# ProDoc_ChisFlash-Prometheus-1_0.net
KiCad netlist of a schematic drawn in EasyEDA Pro
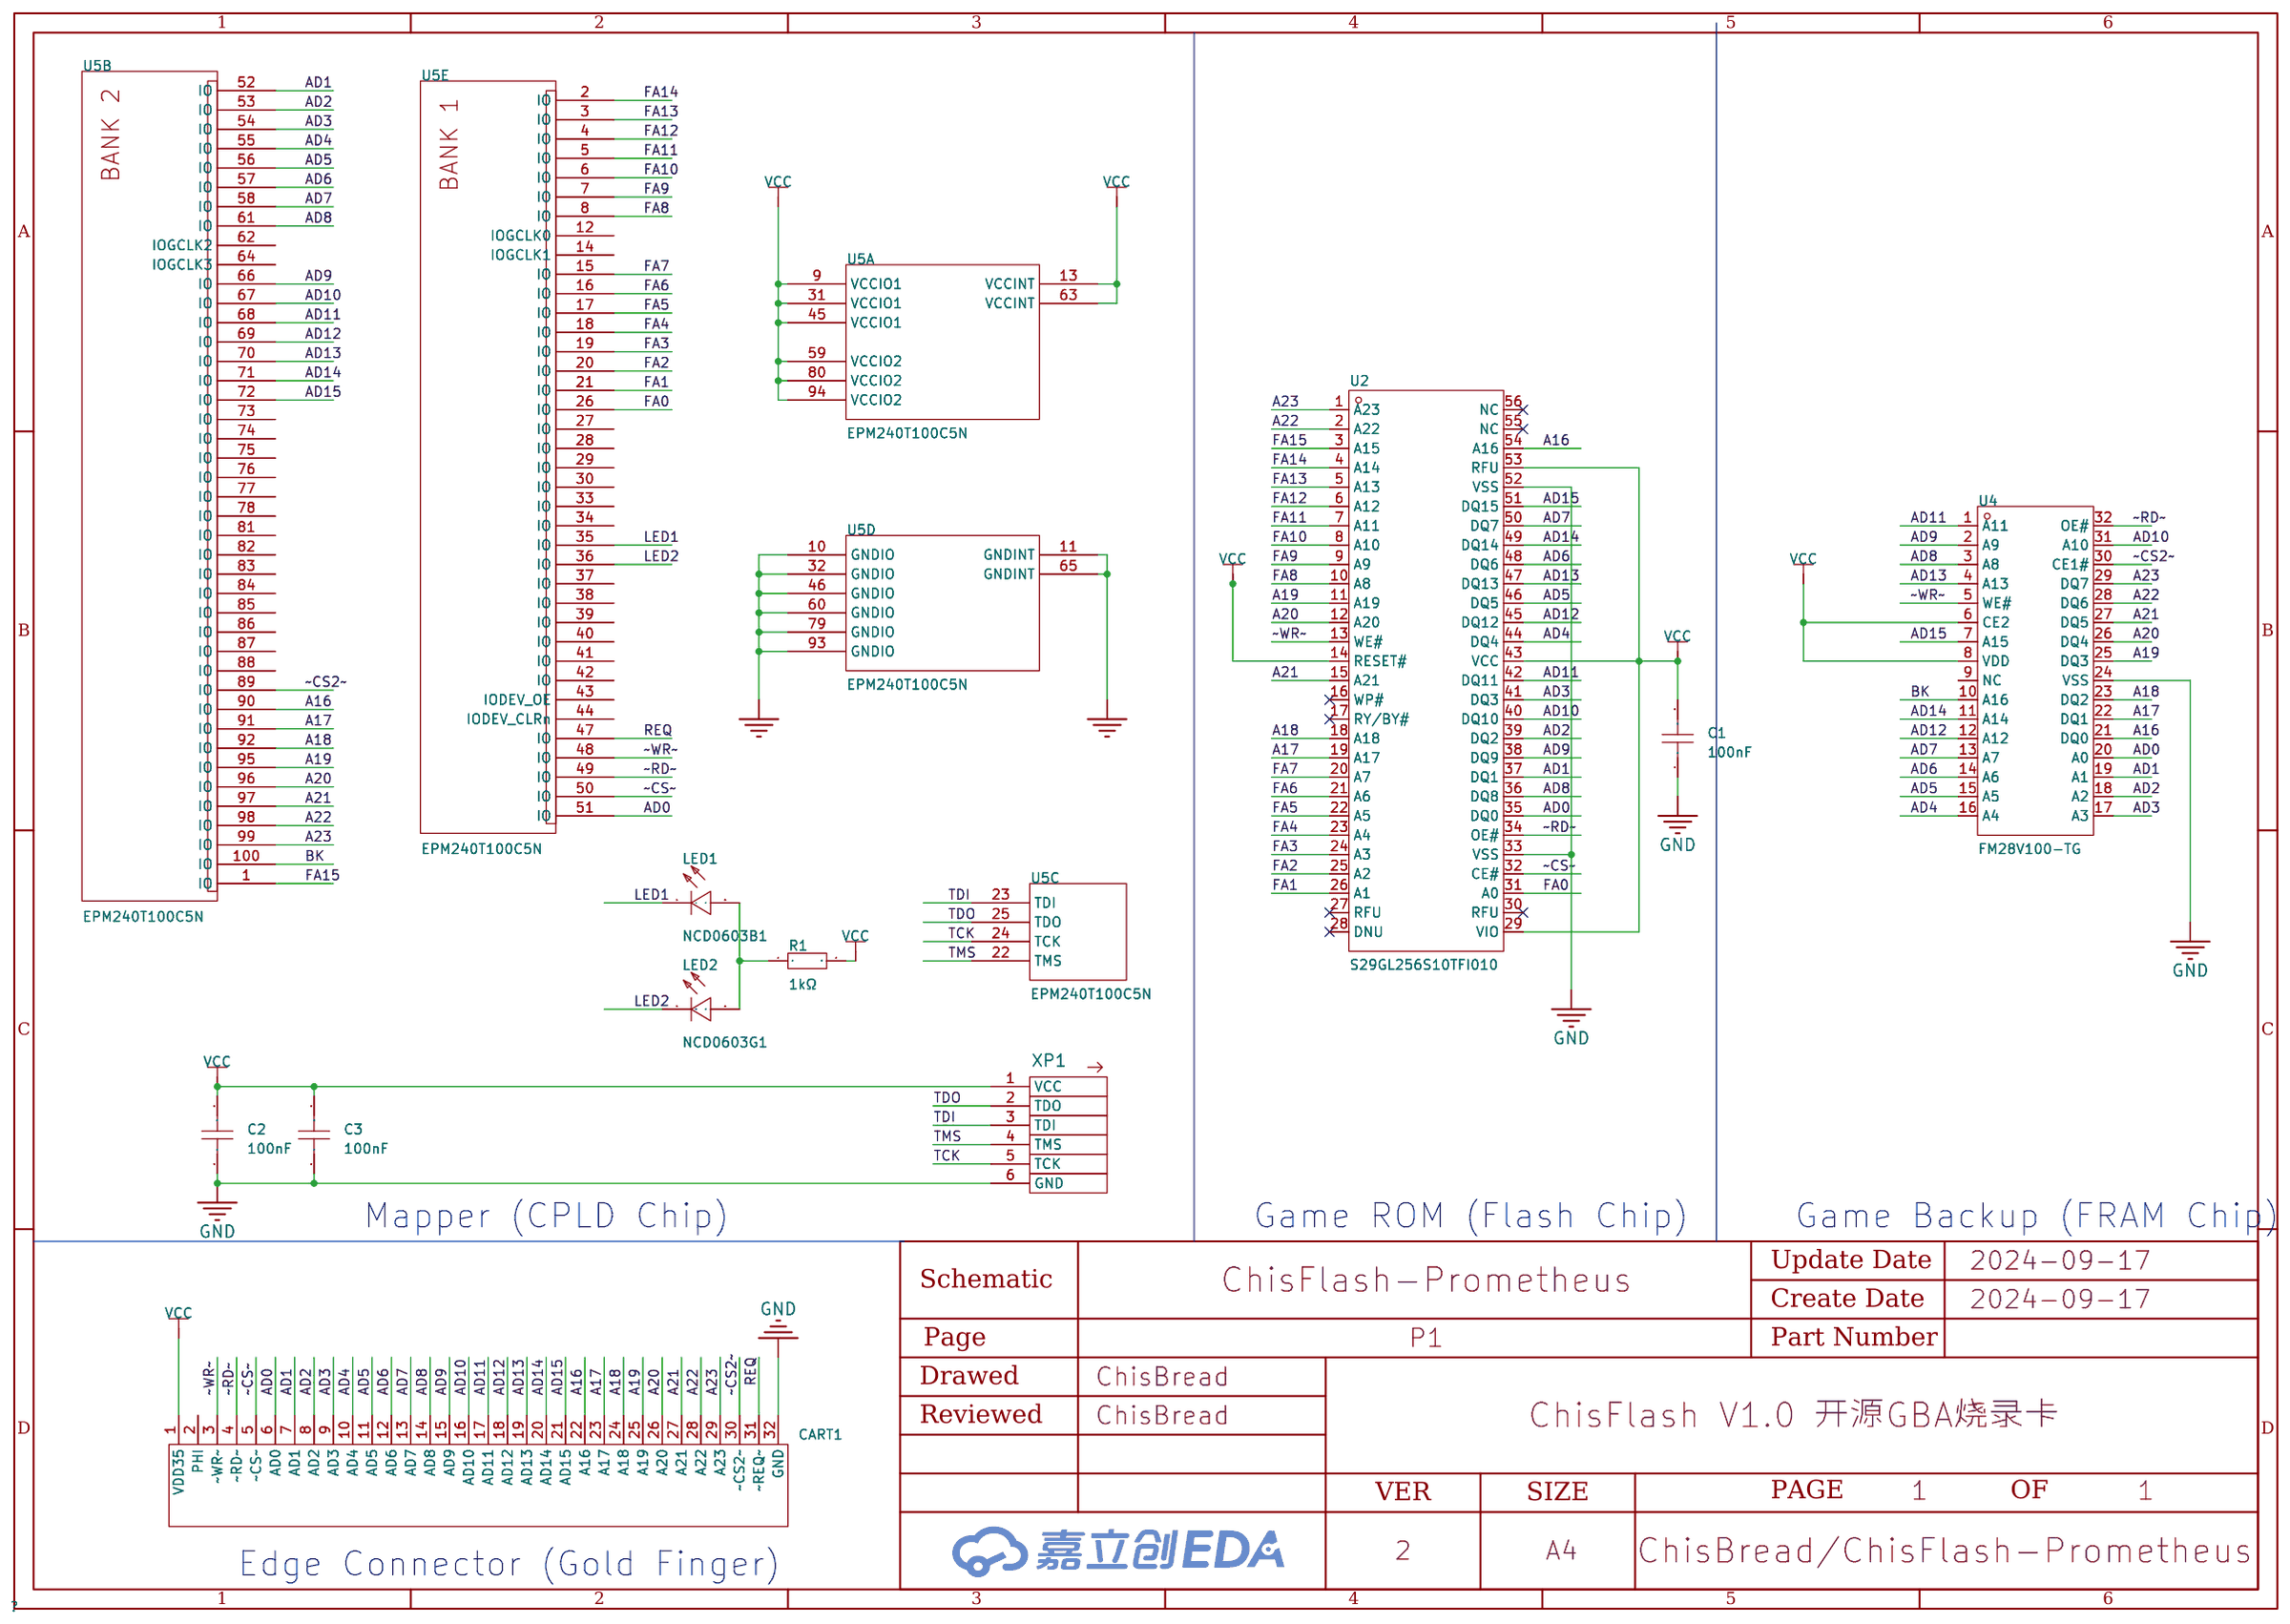
[diagram p0: schematic sheet]

(export (version "E")
  (design (tool "Eeschema 10.0.6"))
  (components
    (comp (ref "C1")
      (value "100nF")
      (footprint "easyedapro:C0603")
      (libsource (lib "easyedapro") (part "CapAcitance"))
    )
    (comp (ref "C2")
      (value "100nF")
      (footprint "easyedapro:C0603")
      (libsource (lib "easyedapro") (part "CapAcitance"))
    )
    (comp (ref "C3")
      (value "100nF")
      (footprint "easyedapro:C0603")
      (libsource (lib "easyedapro") (part "CapAcitance"))
    )
    (comp (ref "CART1")
      (value "~")
      (footprint "easyedapro:GBA卡带金手指")
      (description "GBA卡带金手指")
      (libsource (lib "easyedapro") (part "GBA卡带金手指"))
    )
    (comp (ref "LED1")
      (value "NCD0603B1")
      (footprint "easyedapro:LED0603-RD")
      (fields (field (name "Manufacturer") "国星光电"))
      (libsource (lib "easyedapro") (part "FC-DA1608BK-470H10"))
    )
    (comp (ref "LED2")
      (value "NCD0603G1")
      (footprint "easyedapro:LED0603-RD")
      (fields (field (name "Manufacturer") "国星光电"))
      (libsource (lib "easyedapro") (part "FC-D1608UGK-520D10"))
    )
    (comp (ref "R1")
      (value "1kΩ")
      (footprint "easyedapro:R0603")
      (description "电阻类型:厚膜电阻;阻值:1kΩ;精度:±1%;功率:100mW;最大工作电压:75V;温度系数:±100ppm/°C;")
      (fields
        (field (name "Manufacturer Part") "0603WAF1001T5E")
        (field (name "Manufacturer") "UNI-ROYAL(厚声)")
      )
      (libsource (lib "easyedapro") (part "0603WAF1001T5E"))
    )
    (comp (ref "U2")
      (value "S29GL256S10TFI010")
      (footprint "easyedapro:TSOP-56_L18.4-W14.0-P0.50-LS20.0-TL")
      (fields (field (name "Manufacturer") "SPANSION(飞索)"))
      (libsource (lib "easyedapro") (part "S29GL256S10TFI010"))
    )
    (comp (ref "U4")
      (value "FM28V100-TG")
      (fields (field (name "Manufacturer") "CYPRESS(赛普拉斯)"))
      (libsource (lib "easyedapro") (part "FM28V100-TG_C2959453"))
    )
    (comp (ref "U5")
      (value "EPM240T100C5N")
      (footprint "easyedapro:TQFP-100_L14.0-W14.0-P0.50-LS16.0-BL")
      (description "类型:其它PLD;逻辑门数量:-;逻辑单元数:-;逻辑阵列块数:240;")
      (fields (field (name "Manufacturer") "Intel/Altera"))
      (libsource (lib "easyedapro") (part "EPM240T100C5N"))
    )
    (comp (ref "XP1")
      (value "JTAG")
      (footprint "easyedapro:HDR-TH_6P-P1.27-V-M-1")
      (libsource (lib "easyedapro") (part "jtag"))
    )
  )
  (nets
    (net (code "1") (name "/A16") (class "Default")
      (node (ref "CART1") (pin "22") (pinfunction "A16_22") (pintype "input"))
      (node (ref "U2") (pin "54") (pinfunction "A16_54") (pintype "input"))
      (node (ref "U4") (pin "21") (pinfunction "DQ0_21") (pintype "unspecified"))
      (node (ref "U5") (pin "90") (pinfunction "IO_90") (pintype "bidirectional"))
    )
    (net (code "2") (name "/A17") (class "Default")
      (node (ref "CART1") (pin "23") (pinfunction "A17_23") (pintype "input"))
      (node (ref "U2") (pin "19") (pinfunction "A17_19") (pintype "input"))
      (node (ref "U4") (pin "22") (pinfunction "DQ1_22") (pintype "unspecified"))
      (node (ref "U5") (pin "91") (pinfunction "IO_91") (pintype "bidirectional"))
    )
    (net (code "3") (name "/A18") (class "Default")
      (node (ref "CART1") (pin "24") (pinfunction "A18_24") (pintype "input"))
      (node (ref "U2") (pin "18") (pinfunction "A18_18") (pintype "input"))
      (node (ref "U4") (pin "23") (pinfunction "DQ2_23") (pintype "unspecified"))
      (node (ref "U5") (pin "92") (pinfunction "IO_92") (pintype "bidirectional"))
    )
    (net (code "4") (name "/A19") (class "Default")
      (node (ref "CART1") (pin "25") (pinfunction "A19_25") (pintype "input"))
      (node (ref "U2") (pin "11") (pinfunction "A19_11") (pintype "input"))
      (node (ref "U4") (pin "25") (pinfunction "DQ3_25") (pintype "unspecified"))
      (node (ref "U5") (pin "95") (pinfunction "IO_95") (pintype "bidirectional"))
    )
    (net (code "5") (name "/A20") (class "Default")
      (node (ref "CART1") (pin "26") (pinfunction "A20_26") (pintype "input"))
      (node (ref "U2") (pin "12") (pinfunction "A20_12") (pintype "input"))
      (node (ref "U4") (pin "26") (pinfunction "DQ4_26") (pintype "unspecified"))
      (node (ref "U5") (pin "96") (pinfunction "IO_96") (pintype "bidirectional"))
    )
    (net (code "6") (name "/A21") (class "Default")
      (node (ref "CART1") (pin "27") (pinfunction "A21_27") (pintype "input"))
      (node (ref "U2") (pin "15") (pinfunction "A21_15") (pintype "input"))
      (node (ref "U4") (pin "27") (pinfunction "DQ5_27") (pintype "unspecified"))
      (node (ref "U5") (pin "97") (pinfunction "IO_97") (pintype "bidirectional"))
    )
    (net (code "7") (name "/A22") (class "Default")
      (node (ref "CART1") (pin "28") (pinfunction "A22_28") (pintype "input"))
      (node (ref "U2") (pin "2") (pinfunction "A22_2") (pintype "input"))
      (node (ref "U4") (pin "28") (pinfunction "DQ6_28") (pintype "unspecified"))
      (node (ref "U5") (pin "98") (pinfunction "IO_98") (pintype "bidirectional"))
    )
    (net (code "8") (name "/A23") (class "Default")
      (node (ref "CART1") (pin "29") (pinfunction "A23_29") (pintype "input"))
      (node (ref "U2") (pin "1") (pinfunction "A23_1") (pintype "input"))
      (node (ref "U4") (pin "29") (pinfunction "DQ7_29") (pintype "unspecified"))
      (node (ref "U5") (pin "99") (pinfunction "IO_99") (pintype "bidirectional"))
    )
    (net (code "9") (name "/AD0") (class "Default")
      (node (ref "CART1") (pin "6") (pinfunction "AD0_6") (pintype "input"))
      (node (ref "U2") (pin "35") (pinfunction "DQ0_35") (pintype "input"))
      (node (ref "U4") (pin "20") (pinfunction "A0_20") (pintype "unspecified"))
      (node (ref "U5") (pin "51") (pinfunction "IO_51") (pintype "bidirectional"))
    )
    (net (code "10") (name "/AD1") (class "Default")
      (node (ref "CART1") (pin "7") (pinfunction "AD1_7") (pintype "input"))
      (node (ref "U2") (pin "37") (pinfunction "DQ1_37") (pintype "input"))
      (node (ref "U4") (pin "19") (pinfunction "A1_19") (pintype "unspecified"))
      (node (ref "U5") (pin "52") (pinfunction "IO_52") (pintype "bidirectional"))
    )
    (net (code "11") (name "/AD2") (class "Default")
      (node (ref "CART1") (pin "8") (pinfunction "AD2_8") (pintype "input"))
      (node (ref "U2") (pin "39") (pinfunction "DQ2_39") (pintype "input"))
      (node (ref "U4") (pin "18") (pinfunction "A2_18") (pintype "unspecified"))
      (node (ref "U5") (pin "53") (pinfunction "IO_53") (pintype "bidirectional"))
    )
    (net (code "12") (name "/AD3") (class "Default")
      (node (ref "CART1") (pin "9") (pinfunction "AD3_9") (pintype "input"))
      (node (ref "U2") (pin "41") (pinfunction "DQ3_41") (pintype "input"))
      (node (ref "U4") (pin "17") (pinfunction "A3_17") (pintype "unspecified"))
      (node (ref "U5") (pin "54") (pinfunction "IO_54") (pintype "bidirectional"))
    )
    (net (code "13") (name "/AD4") (class "Default")
      (node (ref "CART1") (pin "10") (pinfunction "AD4_10") (pintype "input"))
      (node (ref "U2") (pin "44") (pinfunction "DQ4_44") (pintype "input"))
      (node (ref "U4") (pin "16") (pinfunction "A4_16") (pintype "unspecified"))
      (node (ref "U5") (pin "55") (pinfunction "IO_55") (pintype "bidirectional"))
    )
    (net (code "14") (name "/AD5") (class "Default")
      (node (ref "CART1") (pin "11") (pinfunction "AD5_11") (pintype "input"))
      (node (ref "U2") (pin "46") (pinfunction "DQ5_46") (pintype "input"))
      (node (ref "U4") (pin "15") (pinfunction "A5_15") (pintype "unspecified"))
      (node (ref "U5") (pin "56") (pinfunction "IO_56") (pintype "bidirectional"))
    )
    (net (code "15") (name "/AD6") (class "Default")
      (node (ref "CART1") (pin "12") (pinfunction "AD6_12") (pintype "input"))
      (node (ref "U2") (pin "48") (pinfunction "DQ6_48") (pintype "input"))
      (node (ref "U4") (pin "14") (pinfunction "A6_14") (pintype "unspecified"))
      (node (ref "U5") (pin "57") (pinfunction "IO_57") (pintype "bidirectional"))
    )
    (net (code "16") (name "/AD7") (class "Default")
      (node (ref "CART1") (pin "13") (pinfunction "AD7_13") (pintype "input"))
      (node (ref "U2") (pin "50") (pinfunction "DQ7_50") (pintype "input"))
      (node (ref "U4") (pin "13") (pinfunction "A7_13") (pintype "unspecified"))
      (node (ref "U5") (pin "58") (pinfunction "IO_58") (pintype "bidirectional"))
    )
    (net (code "17") (name "/AD8") (class "Default")
      (node (ref "CART1") (pin "14") (pinfunction "AD8_14") (pintype "input"))
      (node (ref "U2") (pin "36") (pinfunction "DQ8_36") (pintype "input"))
      (node (ref "U4") (pin "3") (pinfunction "A8_3") (pintype "unspecified"))
      (node (ref "U5") (pin "61") (pinfunction "IO_61") (pintype "bidirectional"))
    )
    (net (code "18") (name "/AD9") (class "Default")
      (node (ref "CART1") (pin "15") (pinfunction "AD9_15") (pintype "input"))
      (node (ref "U2") (pin "38") (pinfunction "DQ9_38") (pintype "input"))
      (node (ref "U4") (pin "2") (pinfunction "A9_2") (pintype "unspecified"))
      (node (ref "U5") (pin "66") (pinfunction "IO_66") (pintype "bidirectional"))
    )
    (net (code "19") (name "/AD10") (class "Default")
      (node (ref "CART1") (pin "16") (pinfunction "AD10_16") (pintype "input"))
      (node (ref "U2") (pin "40") (pinfunction "DQ10_40") (pintype "input"))
      (node (ref "U4") (pin "31") (pinfunction "A10_31") (pintype "unspecified"))
      (node (ref "U5") (pin "67") (pinfunction "IO_67") (pintype "bidirectional"))
    )
    (net (code "20") (name "/AD11") (class "Default")
      (node (ref "CART1") (pin "17") (pinfunction "AD11_17") (pintype "input"))
      (node (ref "U2") (pin "42") (pinfunction "DQ11_42") (pintype "input"))
      (node (ref "U4") (pin "1") (pinfunction "A11_1") (pintype "unspecified"))
      (node (ref "U5") (pin "68") (pinfunction "IO_68") (pintype "bidirectional"))
    )
    (net (code "21") (name "/AD12") (class "Default")
      (node (ref "CART1") (pin "18") (pinfunction "AD12_18") (pintype "input"))
      (node (ref "U2") (pin "45") (pinfunction "DQ12_45") (pintype "input"))
      (node (ref "U4") (pin "12") (pinfunction "A12_12") (pintype "unspecified"))
      (node (ref "U5") (pin "69") (pinfunction "IO_69") (pintype "bidirectional"))
    )
    (net (code "22") (name "/AD13") (class "Default")
      (node (ref "CART1") (pin "19") (pinfunction "AD13_19") (pintype "input"))
      (node (ref "U2") (pin "47") (pinfunction "DQ13_47") (pintype "input"))
      (node (ref "U4") (pin "4") (pinfunction "A13_4") (pintype "unspecified"))
      (node (ref "U5") (pin "70") (pinfunction "IO_70") (pintype "bidirectional"))
    )
    (net (code "23") (name "/AD14") (class "Default")
      (node (ref "CART1") (pin "20") (pinfunction "AD14_20") (pintype "input"))
      (node (ref "U2") (pin "49") (pinfunction "DQ14_49") (pintype "input"))
      (node (ref "U4") (pin "11") (pinfunction "A14_11") (pintype "unspecified"))
      (node (ref "U5") (pin "71") (pinfunction "IO_71") (pintype "bidirectional"))
    )
    (net (code "24") (name "/AD15") (class "Default")
      (node (ref "CART1") (pin "21") (pinfunction "AD15_21") (pintype "input"))
      (node (ref "U2") (pin "51") (pinfunction "DQ15_51") (pintype "input"))
      (node (ref "U4") (pin "7") (pinfunction "A15_7") (pintype "unspecified"))
      (node (ref "U5") (pin "72") (pinfunction "IO_72") (pintype "bidirectional"))
    )
    (net (code "25") (name "/BK") (class "Default")
      (node (ref "U4") (pin "10") (pinfunction "A16_10") (pintype "unspecified"))
      (node (ref "U5") (pin "100") (pinfunction "IO_100") (pintype "bidirectional"))
    )
    (net (code "26") (name "/FA0") (class "Default")
      (node (ref "U2") (pin "31") (pinfunction "A0_31") (pintype "input"))
      (node (ref "U5") (pin "26") (pinfunction "IO_26") (pintype "bidirectional"))
    )
    (net (code "27") (name "/FA1") (class "Default")
      (node (ref "U2") (pin "26") (pinfunction "A1_26") (pintype "input"))
      (node (ref "U5") (pin "21") (pinfunction "IO_21") (pintype "bidirectional"))
    )
    (net (code "28") (name "/FA2") (class "Default")
      (node (ref "U2") (pin "25") (pinfunction "A2_25") (pintype "input"))
      (node (ref "U5") (pin "20") (pinfunction "IO_20") (pintype "bidirectional"))
    )
    (net (code "29") (name "/FA3") (class "Default")
      (node (ref "U2") (pin "24") (pinfunction "A3_24") (pintype "input"))
      (node (ref "U5") (pin "19") (pinfunction "IO_19") (pintype "bidirectional"))
    )
    (net (code "30") (name "/FA4") (class "Default")
      (node (ref "U2") (pin "23") (pinfunction "A4_23") (pintype "input"))
      (node (ref "U5") (pin "18") (pinfunction "IO_18") (pintype "bidirectional"))
    )
    (net (code "31") (name "/FA5") (class "Default")
      (node (ref "U2") (pin "22") (pinfunction "A5_22") (pintype "input"))
      (node (ref "U5") (pin "17") (pinfunction "IO_17") (pintype "bidirectional"))
    )
    (net (code "32") (name "/FA6") (class "Default")
      (node (ref "U2") (pin "21") (pinfunction "A6_21") (pintype "input"))
      (node (ref "U5") (pin "16") (pinfunction "IO_16") (pintype "bidirectional"))
    )
    (net (code "33") (name "/FA7") (class "Default")
      (node (ref "U2") (pin "20") (pinfunction "A7_20") (pintype "input"))
      (node (ref "U5") (pin "15") (pinfunction "IO_15") (pintype "bidirectional"))
    )
    (net (code "34") (name "/FA8") (class "Default")
      (node (ref "U2") (pin "10") (pinfunction "A8_10") (pintype "input"))
      (node (ref "U5") (pin "8") (pinfunction "IO_8") (pintype "bidirectional"))
    )
    (net (code "35") (name "/FA9") (class "Default")
      (node (ref "U2") (pin "9") (pinfunction "A9_9") (pintype "input"))
      (node (ref "U5") (pin "7") (pinfunction "IO_7") (pintype "bidirectional"))
    )
    (net (code "36") (name "/FA10") (class "Default")
      (node (ref "U2") (pin "8") (pinfunction "A10_8") (pintype "input"))
      (node (ref "U5") (pin "6") (pinfunction "IO_6") (pintype "bidirectional"))
    )
    (net (code "37") (name "/FA11") (class "Default")
      (node (ref "U2") (pin "7") (pinfunction "A11_7") (pintype "input"))
      (node (ref "U5") (pin "5") (pinfunction "IO_5") (pintype "bidirectional"))
    )
    (net (code "38") (name "/FA12") (class "Default")
      (node (ref "U2") (pin "6") (pinfunction "A12_6") (pintype "input"))
      (node (ref "U5") (pin "4") (pinfunction "IO_4") (pintype "bidirectional"))
    )
    (net (code "39") (name "/FA13") (class "Default")
      (node (ref "U2") (pin "5") (pinfunction "A13_5") (pintype "input"))
      (node (ref "U5") (pin "3") (pinfunction "IO_3") (pintype "bidirectional"))
    )
    (net (code "40") (name "/FA14") (class "Default")
      (node (ref "U2") (pin "4") (pinfunction "A14_4") (pintype "input"))
      (node (ref "U5") (pin "2") (pinfunction "IO_2") (pintype "bidirectional"))
    )
    (net (code "41") (name "/FA15") (class "Default")
      (node (ref "U2") (pin "3") (pinfunction "A15_3") (pintype "input"))
      (node (ref "U5") (pin "1") (pinfunction "IO_1") (pintype "bidirectional"))
    )
    (net (code "42") (name "/LED1") (class "Default")
      (node (ref "LED1") (pin "1") (pinfunction "-_1") (pintype "input"))
      (node (ref "U5") (pin "35") (pinfunction "IO_35") (pintype "bidirectional"))
    )
    (net (code "43") (name "/LED2") (class "Default")
      (node (ref "LED2") (pin "1") (pinfunction "K_1") (pintype "input"))
      (node (ref "U5") (pin "36") (pinfunction "IO_36") (pintype "bidirectional"))
    )
    (net (code "44") (name "/REQ") (class "Default")
      (node (ref "CART1") (pin "31") (pinfunction "~REQ~_31") (pintype "input"))
      (node (ref "U5") (pin "47") (pinfunction "IO_47") (pintype "bidirectional"))
    )
    (net (code "45") (name "/TCK") (class "Default")
      (node (ref "U5") (pin "24") (pinfunction "TCK_24") (pintype "unspecified"))
      (node (ref "XP1") (pin "5") (pinfunction "TCK_5") (pintype "input"))
    )
    (net (code "46") (name "/TDI") (class "Default")
      (node (ref "U5") (pin "23") (pinfunction "TDI_23") (pintype "unspecified"))
      (node (ref "XP1") (pin "3") (pinfunction "TDI_3") (pintype "output"))
    )
    (net (code "47") (name "/TDO") (class "Default")
      (node (ref "U5") (pin "25") (pinfunction "TDO_25") (pintype "output"))
      (node (ref "XP1") (pin "2") (pinfunction "TDO_2") (pintype "output"))
    )
    (net (code "48") (name "/TMS") (class "Default")
      (node (ref "U5") (pin "22") (pinfunction "TMS_22") (pintype "unspecified"))
      (node (ref "XP1") (pin "4") (pinfunction "TMS_4") (pintype "output"))
    )
    (net (code "49") (name "/~CS2~") (class "Default")
      (node (ref "CART1") (pin "30") (pinfunction "~CS2~_30") (pintype "input"))
      (node (ref "U4") (pin "30") (pinfunction "CE1#_30") (pintype "unspecified"))
      (node (ref "U5") (pin "89") (pinfunction "IO_89") (pintype "bidirectional"))
    )
    (net (code "50") (name "/~CS~") (class "Default")
      (node (ref "CART1") (pin "5") (pinfunction "~CS~_5") (pintype "input"))
      (node (ref "U2") (pin "32") (pinfunction "CE#_32") (pintype "input"))
      (node (ref "U5") (pin "50") (pinfunction "IO_50") (pintype "bidirectional"))
    )
    (net (code "51") (name "/~RD~") (class "Default")
      (node (ref "CART1") (pin "4") (pinfunction "~RD~_4") (pintype "input"))
      (node (ref "U2") (pin "34") (pinfunction "OE#_34") (pintype "input"))
      (node (ref "U4") (pin "32") (pinfunction "OE#_32") (pintype "unspecified"))
      (node (ref "U5") (pin "49") (pinfunction "IO_49") (pintype "bidirectional"))
    )
    (net (code "52") (name "/~WR~") (class "Default")
      (node (ref "CART1") (pin "3") (pinfunction "~WR~_3") (pintype "input"))
      (node (ref "U2") (pin "13") (pinfunction "WE#_13") (pintype "input"))
      (node (ref "U4") (pin "5") (pinfunction "WE#_5") (pintype "unspecified"))
      (node (ref "U5") (pin "48") (pinfunction "IO_48") (pintype "bidirectional"))
    )
    (net (code "53") (name "GND") (class "Default")
      (node (ref "C1") (pin "1") (pinfunction "1_1") (pintype "input"))
      (node (ref "C2") (pin "1") (pinfunction "1_1") (pintype "input"))
      (node (ref "C3") (pin "1") (pinfunction "1_1") (pintype "input"))
      (node (ref "CART1") (pin "32") (pinfunction "GND_32") (pintype "input"))
      (node (ref "U2") (pin "33") (pinfunction "VSS_33") (pintype "input"))
      (node (ref "U2") (pin "52") (pinfunction "VSS_52") (pintype "input"))
      (node (ref "U4") (pin "24") (pinfunction "VSS_24") (pintype "unspecified"))
      (node (ref "U5") (pin "10") (pinfunction "GNDIO_10") (pintype "unspecified"))
      (node (ref "U5") (pin "11") (pinfunction "GNDINT_11") (pintype "unspecified"))
      (node (ref "U5") (pin "32") (pinfunction "GNDIO_32") (pintype "unspecified"))
      (node (ref "U5") (pin "46") (pinfunction "GNDIO_46") (pintype "unspecified"))
      (node (ref "U5") (pin "60") (pinfunction "GNDIO_60") (pintype "unspecified"))
      (node (ref "U5") (pin "65") (pinfunction "GNDINT_65") (pintype "unspecified"))
      (node (ref "U5") (pin "79") (pinfunction "GNDIO_79") (pintype "unspecified"))
      (node (ref "U5") (pin "93") (pinfunction "GNDIO_93") (pintype "unspecified"))
      (node (ref "XP1") (pin "6") (pinfunction "GND_6") (pintype "input"))
    )
    (net (code "54") (name "Net-(LED1-+)") (class "Default")
      (node (ref "LED1") (pin "2") (pinfunction "+_2") (pintype "input"))
      (node (ref "LED2") (pin "2") (pinfunction "A_2") (pintype "input"))
      (node (ref "R1") (pin "1") (pinfunction "1_1") (pintype "input"))
    )
    (net (code "55") (name "VCC") (class "Default")
      (node (ref "C1") (pin "2") (pinfunction "2_2") (pintype "input"))
      (node (ref "C2") (pin "2") (pinfunction "2_2") (pintype "input"))
      (node (ref "C3") (pin "2") (pinfunction "2_2") (pintype "input"))
      (node (ref "CART1") (pin "1") (pinfunction "VDD35_1") (pintype "input"))
      (node (ref "R1") (pin "2") (pinfunction "2_2") (pintype "input"))
      (node (ref "U2") (pin "14") (pinfunction "RESET#_14") (pintype "input"))
      (node (ref "U2") (pin "29") (pinfunction "VIO_29") (pintype "input"))
      (node (ref "U2") (pin "43") (pinfunction "VCC_43") (pintype "input"))
      (node (ref "U2") (pin "53") (pinfunction "RFU_53") (pintype "input"))
      (node (ref "U4") (pin "6") (pinfunction "CE2_6") (pintype "unspecified"))
      (node (ref "U4") (pin "8") (pinfunction "VDD_8") (pintype "unspecified"))
      (node (ref "U5") (pin "13") (pinfunction "VCCINT_13") (pintype "unspecified"))
      (node (ref "U5") (pin "31") (pinfunction "VCCIO1_31") (pintype "unspecified"))
      (node (ref "U5") (pin "45") (pinfunction "VCCIO1_45") (pintype "unspecified"))
      (node (ref "U5") (pin "59") (pinfunction "VCCIO2_59") (pintype "unspecified"))
      (node (ref "U5") (pin "63") (pinfunction "VCCINT_63") (pintype "unspecified"))
      (node (ref "U5") (pin "80") (pinfunction "VCCIO2_80") (pintype "unspecified"))
      (node (ref "U5") (pin "9") (pinfunction "VCCIO1_9") (pintype "unspecified"))
      (node (ref "U5") (pin "94") (pinfunction "VCCIO2_94") (pintype "unspecified"))
      (node (ref "XP1") (pin "1") (pinfunction "VCC_1") (pintype "output"))
    )
    (net (code "56") (name "unconnected-(CART1-PHI-Pad2)") (class "Default")
      (node (ref "CART1") (pin "2") (pinfunction "PHI_2") (pintype "input"))
    )
    (net (code "57") (name "unconnected-(U2-DNU-Pad28)") (class "Default")
      (node (ref "U2") (pin "28") (pinfunction "DNU_28") (pintype "input+no_connect"))
    )
    (net (code "58") (name "unconnected-(U2-NC-Pad55)") (class "Default")
      (node (ref "U2") (pin "55") (pinfunction "NC_55") (pintype "input+no_connect"))
    )
    (net (code "59") (name "unconnected-(U2-NC-Pad56)") (class "Default")
      (node (ref "U2") (pin "56") (pinfunction "NC_56") (pintype "input+no_connect"))
    )
    (net (code "60") (name "unconnected-(U2-RFU-Pad27)") (class "Default")
      (node (ref "U2") (pin "27") (pinfunction "RFU_27") (pintype "input+no_connect"))
    )
    (net (code "61") (name "unconnected-(U2-RFU-Pad30)") (class "Default")
      (node (ref "U2") (pin "30") (pinfunction "RFU_30") (pintype "input+no_connect"))
    )
    (net (code "62") (name "unconnected-(U2-RY{slash}BY#-Pad17)") (class "Default")
      (node (ref "U2") (pin "17") (pinfunction "RY/BY#_17") (pintype "input+no_connect"))
    )
    (net (code "63") (name "unconnected-(U2-WP#-Pad16)") (class "Default")
      (node (ref "U2") (pin "16") (pinfunction "WP#_16") (pintype "input+no_connect"))
    )
    (net (code "64") (name "unconnected-(U4-NC-Pad9)") (class "Default")
      (node (ref "U4") (pin "9") (pinfunction "NC_9") (pintype "unspecified"))
    )
    (net (code "65") (name "unconnected-(U5B-IO-Pad73)") (class "Default")
      (node (ref "U5") (pin "73") (pinfunction "IO_73") (pintype "bidirectional"))
    )
    (net (code "66") (name "unconnected-(U5B-IO-Pad74)") (class "Default")
      (node (ref "U5") (pin "74") (pinfunction "IO_74") (pintype "bidirectional"))
    )
    (net (code "67") (name "unconnected-(U5B-IO-Pad75)") (class "Default")
      (node (ref "U5") (pin "75") (pinfunction "IO_75") (pintype "bidirectional"))
    )
    (net (code "68") (name "unconnected-(U5B-IO-Pad76)") (class "Default")
      (node (ref "U5") (pin "76") (pinfunction "IO_76") (pintype "bidirectional"))
    )
    (net (code "69") (name "unconnected-(U5B-IO-Pad77)") (class "Default")
      (node (ref "U5") (pin "77") (pinfunction "IO_77") (pintype "bidirectional"))
    )
    (net (code "70") (name "unconnected-(U5B-IO-Pad78)") (class "Default")
      (node (ref "U5") (pin "78") (pinfunction "IO_78") (pintype "bidirectional"))
    )
    (net (code "71") (name "unconnected-(U5B-IO-Pad81)") (class "Default")
      (node (ref "U5") (pin "81") (pinfunction "IO_81") (pintype "bidirectional"))
    )
    (net (code "72") (name "unconnected-(U5B-IO-Pad82)") (class "Default")
      (node (ref "U5") (pin "82") (pinfunction "IO_82") (pintype "bidirectional"))
    )
    (net (code "73") (name "unconnected-(U5B-IO-Pad83)") (class "Default")
      (node (ref "U5") (pin "83") (pinfunction "IO_83") (pintype "bidirectional"))
    )
    (net (code "74") (name "unconnected-(U5B-IO-Pad84)") (class "Default")
      (node (ref "U5") (pin "84") (pinfunction "IO_84") (pintype "bidirectional"))
    )
    (net (code "75") (name "unconnected-(U5B-IO-Pad85)") (class "Default")
      (node (ref "U5") (pin "85") (pinfunction "IO_85") (pintype "bidirectional"))
    )
    (net (code "76") (name "unconnected-(U5B-IO-Pad86)") (class "Default")
      (node (ref "U5") (pin "86") (pinfunction "IO_86") (pintype "bidirectional"))
    )
    (net (code "77") (name "unconnected-(U5B-IO-Pad87)") (class "Default")
      (node (ref "U5") (pin "87") (pinfunction "IO_87") (pintype "bidirectional"))
    )
    (net (code "78") (name "unconnected-(U5B-IO-Pad88)") (class "Default")
      (node (ref "U5") (pin "88") (pinfunction "IO_88") (pintype "bidirectional"))
    )
    (net (code "79") (name "unconnected-(U5B-IOGCLK2-Pad62)") (class "Default")
      (node (ref "U5") (pin "62") (pinfunction "IOGCLK2_62") (pintype "bidirectional"))
    )
    (net (code "80") (name "unconnected-(U5B-IOGCLK3-Pad64)") (class "Default")
      (node (ref "U5") (pin "64") (pinfunction "IOGCLK3_64") (pintype "bidirectional"))
    )
    (net (code "81") (name "unconnected-(U5E-IO-Pad27)") (class "Default")
      (node (ref "U5") (pin "27") (pinfunction "IO_27") (pintype "bidirectional"))
    )
    (net (code "82") (name "unconnected-(U5E-IO-Pad28)") (class "Default")
      (node (ref "U5") (pin "28") (pinfunction "IO_28") (pintype "bidirectional"))
    )
    (net (code "83") (name "unconnected-(U5E-IO-Pad29)") (class "Default")
      (node (ref "U5") (pin "29") (pinfunction "IO_29") (pintype "bidirectional"))
    )
    (net (code "84") (name "unconnected-(U5E-IO-Pad30)") (class "Default")
      (node (ref "U5") (pin "30") (pinfunction "IO_30") (pintype "bidirectional"))
    )
    (net (code "85") (name "unconnected-(U5E-IO-Pad33)") (class "Default")
      (node (ref "U5") (pin "33") (pinfunction "IO_33") (pintype "bidirectional"))
    )
    (net (code "86") (name "unconnected-(U5E-IO-Pad34)") (class "Default")
      (node (ref "U5") (pin "34") (pinfunction "IO_34") (pintype "bidirectional"))
    )
    (net (code "87") (name "unconnected-(U5E-IO-Pad37)") (class "Default")
      (node (ref "U5") (pin "37") (pinfunction "IO_37") (pintype "bidirectional"))
    )
    (net (code "88") (name "unconnected-(U5E-IO-Pad38)") (class "Default")
      (node (ref "U5") (pin "38") (pinfunction "IO_38") (pintype "bidirectional"))
    )
    (net (code "89") (name "unconnected-(U5E-IO-Pad39)") (class "Default")
      (node (ref "U5") (pin "39") (pinfunction "IO_39") (pintype "bidirectional"))
    )
    (net (code "90") (name "unconnected-(U5E-IO-Pad40)") (class "Default")
      (node (ref "U5") (pin "40") (pinfunction "IO_40") (pintype "bidirectional"))
    )
    (net (code "91") (name "unconnected-(U5E-IO-Pad41)") (class "Default")
      (node (ref "U5") (pin "41") (pinfunction "IO_41") (pintype "bidirectional"))
    )
    (net (code "92") (name "unconnected-(U5E-IO-Pad42)") (class "Default")
      (node (ref "U5") (pin "42") (pinfunction "IO_42") (pintype "bidirectional"))
    )
    (net (code "93") (name "unconnected-(U5E-IODEV_CLRn-Pad44)") (class "Default")
      (node (ref "U5") (pin "44") (pinfunction "IODEV_CLRn_44") (pintype "bidirectional"))
    )
    (net (code "94") (name "unconnected-(U5E-IODEV_OE-Pad43)") (class "Default")
      (node (ref "U5") (pin "43") (pinfunction "IODEV_OE_43") (pintype "bidirectional"))
    )
    (net (code "95") (name "unconnected-(U5E-IOGCLK0-Pad12)") (class "Default")
      (node (ref "U5") (pin "12") (pinfunction "IOGCLK0_12") (pintype "bidirectional"))
    )
    (net (code "96") (name "unconnected-(U5E-IOGCLK1-Pad14)") (class "Default")
      (node (ref "U5") (pin "14") (pinfunction "IOGCLK1_14") (pintype "bidirectional"))
    )
  )
)
